# 02_Power.net
KiCad netlist of a schematic drawn in Altium Designer
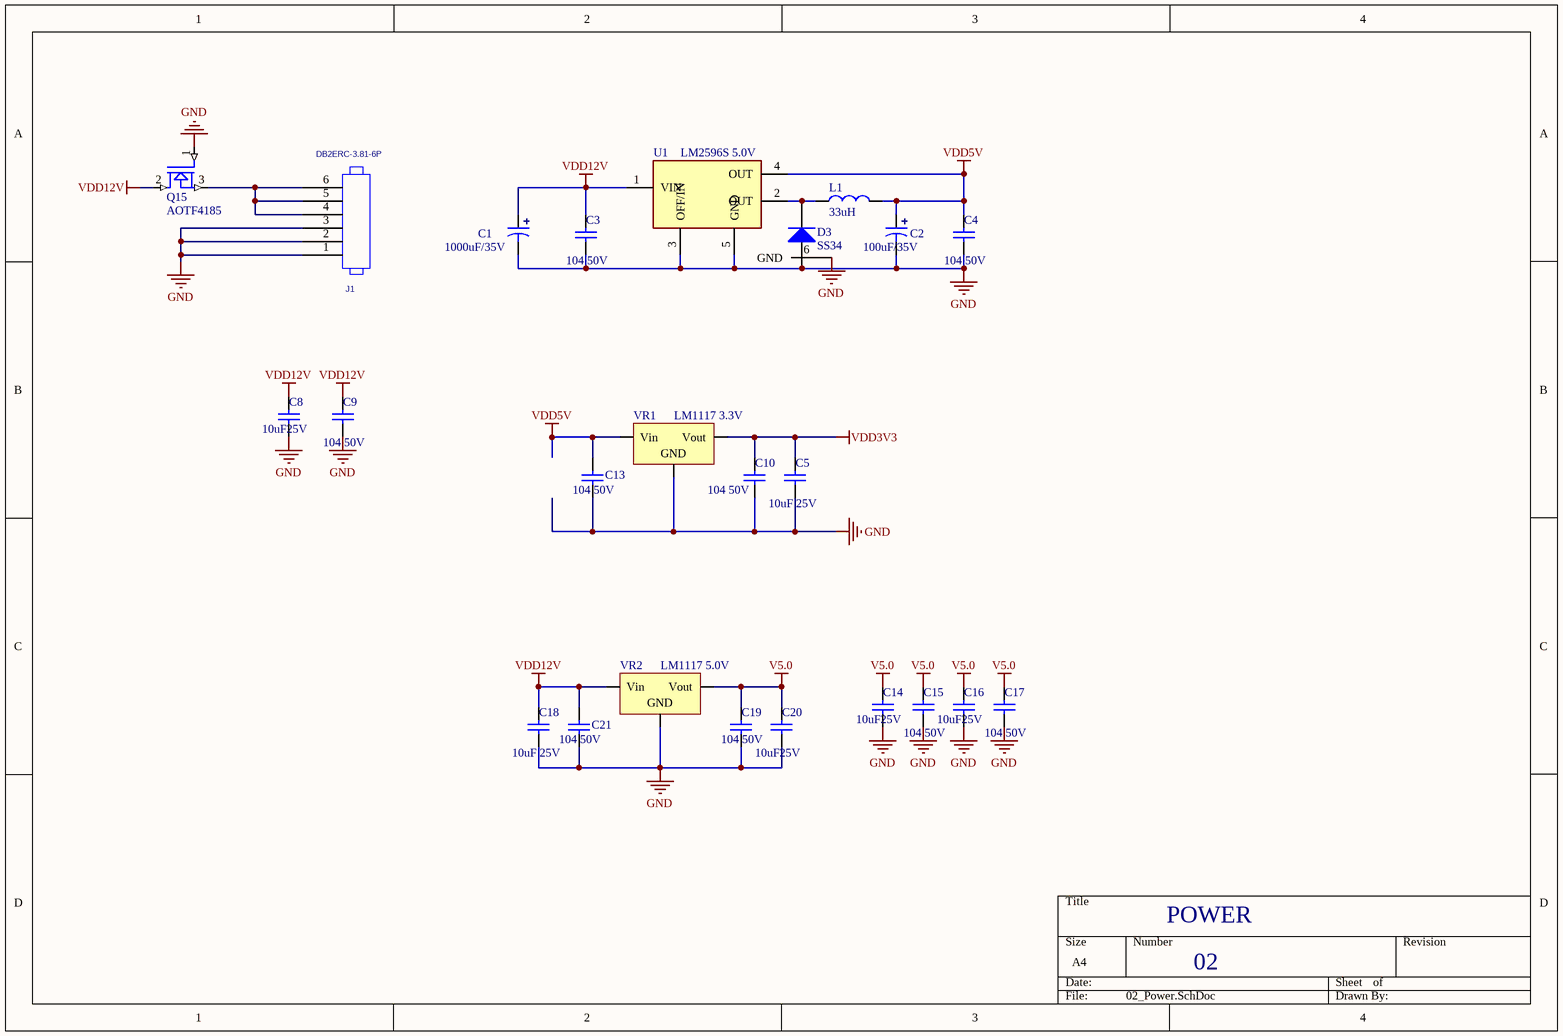
[diagram p0: 02_Power.SchDoc]

(export (version "E")
  (design (tool "Eeschema 10.0.6"))
  (components
    (comp (ref "C1")
      (value "1000uF/35V")
      (footprint "10*16")
      (description "电解电容")
      (libsource (lib "XiaoyI") (part "CAP2"))
    )
    (comp (ref "C2")
      (value "100uF/35V")
      (footprint "6*8")
      (description "电解电容")
      (libsource (lib "XiaoyI") (part "CAP2"))
    )
    (comp (ref "C3")
      (value "104 50V")
      (footprint "SMD-0805C")
      (description "贴片电容 10%")
      (libsource (lib "XiaoyI") (part "CAP4"))
    )
    (comp (ref "C4")
      (value "104 50V")
      (footprint "SMD-0805C")
      (description "贴片电容 10%")
      (libsource (lib "XiaoyI") (part "CAP4"))
    )
    (comp (ref "C5")
      (value "10uF 25V")
      (footprint "SMD-0603C")
      (description "贴片电容 20%")
      (libsource (lib "XiaoyI") (part "CAP4"))
    )
    (comp (ref "C8")
      (value "10uF25V")
      (footprint "SMD-0603C")
      (description "贴片电容 10%")
      (libsource (lib "XiaoyI") (part "CAP4"))
    )
    (comp (ref "C9")
      (value "104 50V")
      (footprint "SMD-0603C")
      (description "贴片电容 10%")
      (libsource (lib "XiaoyI") (part "CAP4"))
    )
    (comp (ref "C10")
      (value "104 50V")
      (footprint "SMD-0603C")
      (description "贴片电容 10%")
      (libsource (lib "XiaoyI") (part "CAP4"))
    )
    (comp (ref "C13")
      (value "104 50V")
      (footprint "SMD-0603C")
      (description "贴片电容 10%")
      (libsource (lib "XiaoyI") (part "CAP4"))
    )
    (comp (ref "C14")
      (value "10uF25V")
      (footprint "SMD-0603C")
      (description "贴片电容 20%")
      (libsource (lib "XiaoyI") (part "CAP4"))
    )
    (comp (ref "C15")
      (value "104 50V")
      (footprint "SMD-0603C")
      (description "贴片电容 20%")
      (libsource (lib "XiaoyI") (part "CAP4"))
    )
    (comp (ref "C16")
      (value "10uF25V")
      (footprint "SMD-0603C")
      (description "贴片电容 20%")
      (libsource (lib "XiaoyI") (part "CAP4"))
    )
    (comp (ref "C17")
      (value "104 50V")
      (footprint "SMD-0603C")
      (description "贴片电容 20%")
      (libsource (lib "XiaoyI") (part "CAP4"))
    )
    (comp (ref "C18")
      (value "10uF 25V")
      (footprint "SMD-0603C")
      (description "贴片电容 20%")
      (libsource (lib "XiaoyI") (part "CAP4"))
    )
    (comp (ref "C19")
      (value "104 50V")
      (footprint "SMD-0603C")
      (description "贴片电容 20%")
      (libsource (lib "XiaoyI") (part "CAP4"))
    )
    (comp (ref "C20")
      (value "10uF25V")
      (footprint "SMD-0603C")
      (description "贴片电容 20%")
      (libsource (lib "XiaoyI") (part "CAP4"))
    )
    (comp (ref "C21")
      (value "104 50V")
      (footprint "SMD-0603C")
      (description "贴片电容 20%")
      (libsource (lib "XiaoyI") (part "CAP4"))
    )
    (comp (ref "D3") (value "SS34") (footprint "SMA") (libsource (lib "Sch_library") (part "DIODE")))
    (comp (ref "J1")
      (value "DB2ERC-3.81-6P")
      (footprint "VH-AW-3.96*6P")
      (fields (field (name "Comment") "HEADER_6"))
      (libsource (lib "liujingtao_V1.0") (part "HEADER_6"))
    )
    (comp (ref "L1") (value "33uH") (footprint "CDRH-127") (libsource (lib "Sch_library") (part "IND")))
    (comp (ref "Q15")
      (value "AOTF4185")
      (footprint "to220")
      (description "MOSFET N")
      (libsource (lib "XiaoyI") (part "MOSFET N"))
    )
    (comp (ref "U1")
      (value "LM2596S 5.0V")
      (footprint "TO-263-5")
      (libsource (lib "Sch_library") (part "LM2596"))
    )
    (comp (ref "VR1")
      (value "LM1117 3.3V")
      (footprint "SOT223")
      (description "三端稳压器")
      (libsource (lib "XiaoyI") (part "LM1117"))
    )
    (comp (ref "VR2")
      (value "LM1117 5.0V")
      (footprint "SOT223")
      (description "三端稳压器 （耐压20V）")
      (libsource (lib "XiaoyI") (part "LM1117"))
    )
  )
  (nets
    (net (code "1") (name "GND") (class "Default")
      (node (ref "C1") (pin "2") (pinfunction "2_2") (pintype "passive"))
      (node (ref "C10") (pin "1") (pinfunction "1_1") (pintype "passive"))
      (node (ref "C13") (pin "1") (pinfunction "1_1") (pintype "passive"))
      (node (ref "C14") (pin "1") (pinfunction "1_1") (pintype "passive"))
      (node (ref "C15") (pin "1") (pinfunction "1_1") (pintype "passive"))
      (node (ref "C16") (pin "1") (pinfunction "1_1") (pintype "passive"))
      (node (ref "C17") (pin "1") (pinfunction "1_1") (pintype "passive"))
      (node (ref "C18") (pin "1") (pinfunction "1_1") (pintype "passive"))
      (node (ref "C19") (pin "1") (pinfunction "1_1") (pintype "passive"))
      (node (ref "C2") (pin "2") (pinfunction "2_2") (pintype "passive"))
      (node (ref "C20") (pin "1") (pinfunction "1_1") (pintype "passive"))
      (node (ref "C21") (pin "1") (pinfunction "1_1") (pintype "passive"))
      (node (ref "C3") (pin "1") (pinfunction "1_1") (pintype "passive"))
      (node (ref "C4") (pin "1") (pinfunction "1_1") (pintype "passive"))
      (node (ref "C5") (pin "1") (pinfunction "1_1") (pintype "passive"))
      (node (ref "C8") (pin "1") (pinfunction "1_1") (pintype "passive"))
      (node (ref "C9") (pin "1") (pinfunction "1_1") (pintype "passive"))
      (node (ref "D3") (pin "1") (pinfunction "A_1") (pintype "passive"))
      (node (ref "J1") (pin "1") (pinfunction "1_1") (pintype "passive"))
      (node (ref "J1") (pin "2") (pinfunction "2_2") (pintype "passive"))
      (node (ref "J1") (pin "3") (pinfunction "3_3") (pintype "passive"))
      (node (ref "Q15") (pin "1") (pinfunction "G_1") (pintype "input"))
      (node (ref "U1") (pin "3") (pinfunction "OFF/IN_3") (pintype "passive"))
      (node (ref "U1") (pin "5") (pinfunction "GND_5") (pintype "passive"))
      (node (ref "U1") (pin "6") (pinfunction "GND_6") (pintype "passive"))
      (node (ref "VR1") (pin "1") (pinfunction "GND_1") (pintype "passive"))
      (node (ref "VR2") (pin "1") (pinfunction "GND_1") (pintype "passive"))
    )
    (net (code "2") (name "Net-(D3-K)") (class "Default")
      (node (ref "D3") (pin "2") (pinfunction "K_2") (pintype "passive"))
      (node (ref "L1") (pin "1") (pinfunction "1_1") (pintype "passive"))
      (node (ref "U1") (pin "2") (pinfunction "OUT_2") (pintype "passive"))
    )
    (net (code "3") (name "Net-(Q15-S)") (class "Default")
      (node (ref "J1") (pin "4") (pinfunction "4_4") (pintype "passive"))
      (node (ref "J1") (pin "5") (pinfunction "5_5") (pintype "passive"))
      (node (ref "J1") (pin "6") (pinfunction "6_6") (pintype "passive"))
      (node (ref "Q15") (pin "3") (pinfunction "S_3") (pintype "output"))
    )
    (net (code "4") (name "V5.0") (class "Default")
      (node (ref "C14") (pin "2") (pinfunction "2_2") (pintype "passive"))
      (node (ref "C15") (pin "2") (pinfunction "2_2") (pintype "passive"))
      (node (ref "C16") (pin "2") (pinfunction "2_2") (pintype "passive"))
      (node (ref "C17") (pin "2") (pinfunction "2_2") (pintype "passive"))
      (node (ref "C19") (pin "2") (pinfunction "2_2") (pintype "passive"))
      (node (ref "C20") (pin "2") (pinfunction "2_2") (pintype "passive"))
      (node (ref "VR2") (pin "2") (pinfunction "Vout_2") (pintype "passive"))
    )
    (net (code "5") (name "VDD3V3") (class "Default")
      (node (ref "C10") (pin "2") (pinfunction "2_2") (pintype "passive"))
      (node (ref "C5") (pin "2") (pinfunction "2_2") (pintype "passive"))
      (node (ref "VR1") (pin "2") (pinfunction "Vout_2") (pintype "passive"))
    )
    (net (code "6") (name "VDD5V") (class "Default")
      (node (ref "C13") (pin "2") (pinfunction "2_2") (pintype "passive"))
      (node (ref "C2") (pin "1") (pinfunction "1_1") (pintype "passive"))
      (node (ref "C4") (pin "2") (pinfunction "2_2") (pintype "passive"))
      (node (ref "L1") (pin "2") (pinfunction "2_2") (pintype "passive"))
      (node (ref "U1") (pin "4") (pinfunction "OUT_4") (pintype "passive"))
      (node (ref "VR1") (pin "3") (pinfunction "Vin_3") (pintype "passive"))
    )
    (net (code "7") (name "VDD12V") (class "Default")
      (node (ref "C1") (pin "1") (pinfunction "1_1") (pintype "passive"))
      (node (ref "C18") (pin "2") (pinfunction "2_2") (pintype "passive"))
      (node (ref "C21") (pin "2") (pinfunction "2_2") (pintype "passive"))
      (node (ref "C3") (pin "2") (pinfunction "2_2") (pintype "passive"))
      (node (ref "C8") (pin "2") (pinfunction "2_2") (pintype "passive"))
      (node (ref "C9") (pin "2") (pinfunction "2_2") (pintype "passive"))
      (node (ref "Q15") (pin "2") (pinfunction "D_2") (pintype "input"))
      (node (ref "U1") (pin "1") (pinfunction "VIN_1") (pintype "passive"))
      (node (ref "VR2") (pin "3") (pinfunction "Vin_3") (pintype "passive"))
    )
  )
)
